# TIA_For_Photodiode.net
KiCad netlist of a schematic drawn in Altium Designer
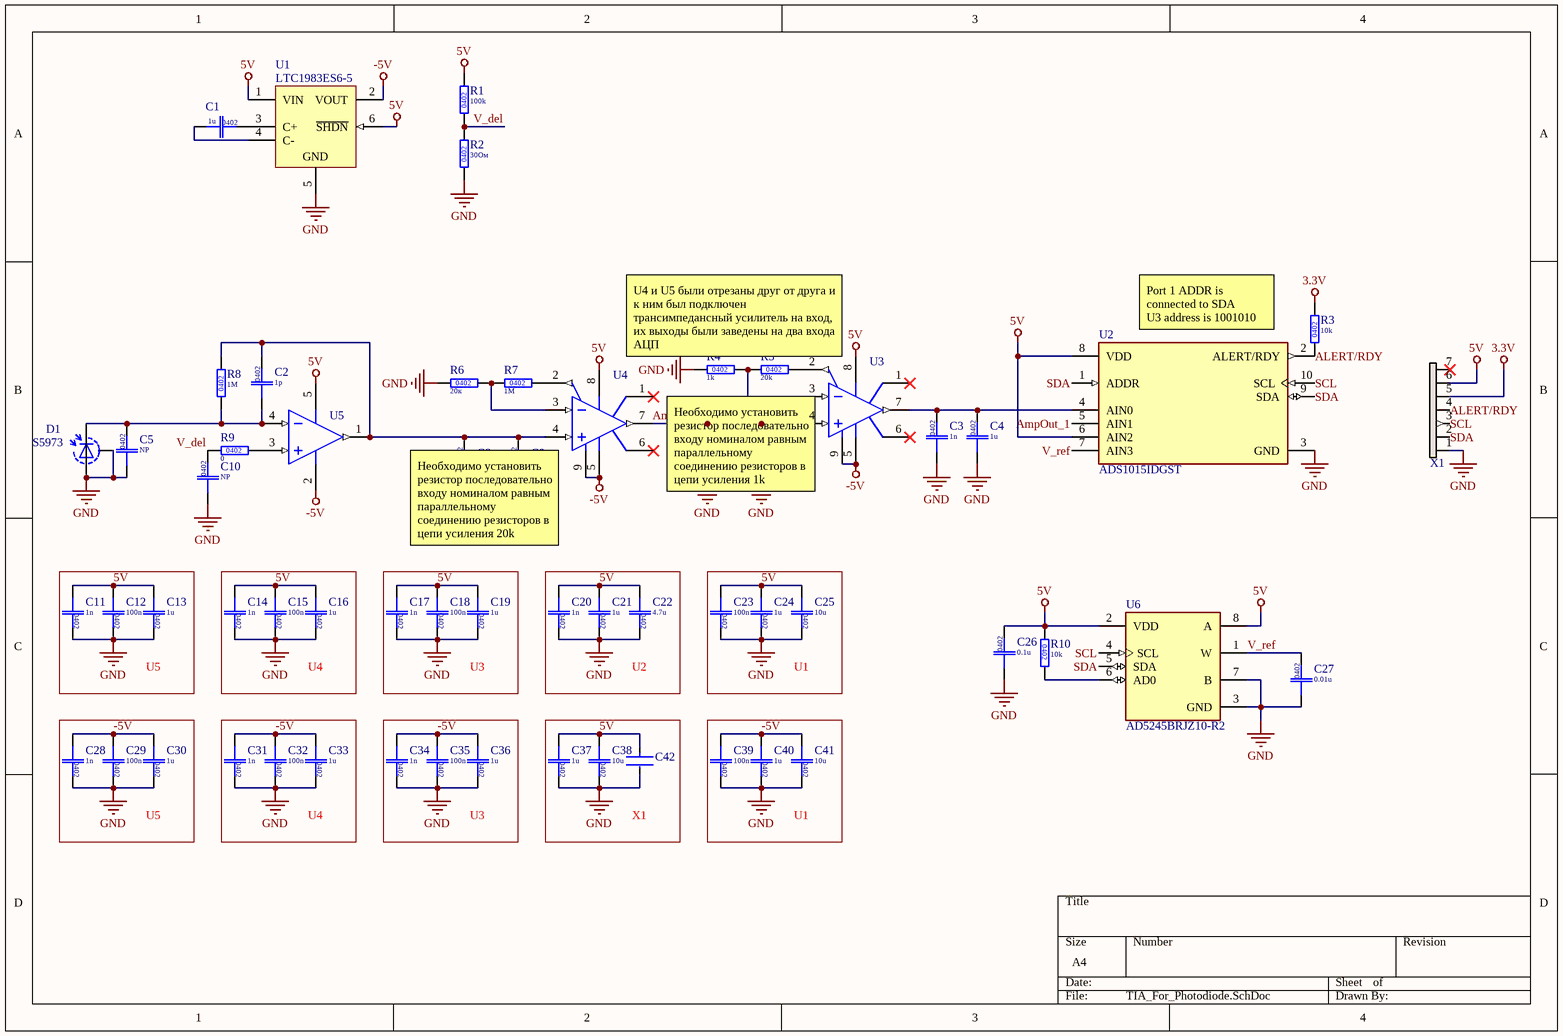
[diagram p0: TIA_For_Photodiode.SchDoc]

(export (version "E")
  (design (tool "Eeschema 10.0.6"))
  (components
    (comp (ref "C1")
      (value "1u")
      (footprint "SMD 0402")
      (fields (field (name "TOLERANCE") "10%") (field (name "VOLTAGE") "25v"))
      (libsource (lib "ComponentsDatabase") (part "Capacitor 0402"))
    )
    (comp (ref "C2")
      (value "1p")
      (footprint "SMD 0402")
      (fields (field (name "TOLERANCE") "20%") (field (name "VOLTAGE") "6,3v"))
      (libsource (lib "ComponentsDatabase") (part "Capacitor 0402"))
    )
    (comp (ref "C3")
      (value "1n")
      (footprint "SMD 0402")
      (fields (field (name "TOLERANCE") "20%") (field (name "VOLTAGE") "6,3v"))
      (libsource (lib "ComponentsDatabase") (part "Capacitor 0402"))
    )
    (comp (ref "C4")
      (value "1u")
      (footprint "SMD 0402")
      (fields (field (name "TOLERANCE") "20%") (field (name "VOLTAGE") "6,3v"))
      (libsource (lib "ComponentsDatabase") (part "Capacitor 0402"))
    )
    (comp (ref "C5")
      (value "NP")
      (footprint "SMD 0402")
      (fields (field (name "TOLERANCE") "20%") (field (name "VOLTAGE") "6,3v"))
      (libsource (lib "ComponentsDatabase") (part "Capacitor 0402"))
    )
    (comp (ref "C6")
      (value "1n")
      (footprint "SMD 0402")
      (fields (field (name "TOLERANCE") "20%") (field (name "VOLTAGE") "6,3v"))
      (libsource (lib "ComponentsDatabase") (part "Capacitor 0402"))
    )
    (comp (ref "C7")
      (value "1u")
      (footprint "SMD 0402")
      (fields (field (name "TOLERANCE") "20%") (field (name "VOLTAGE") "6,3v"))
      (libsource (lib "ComponentsDatabase") (part "Capacitor 0402"))
    )
    (comp (ref "C8")
      (value "1n")
      (footprint "SMD 0402")
      (fields (field (name "TOLERANCE") "20%") (field (name "VOLTAGE") "6,3v"))
      (libsource (lib "ComponentsDatabase") (part "Capacitor 0402"))
    )
    (comp (ref "C9")
      (value "1u")
      (footprint "SMD 0402")
      (fields (field (name "TOLERANCE") "20%") (field (name "VOLTAGE") "6,3v"))
      (libsource (lib "ComponentsDatabase") (part "Capacitor 0402"))
    )
    (comp (ref "C10")
      (value "NP")
      (footprint "SMD 0402")
      (fields (field (name "TOLERANCE") "20%") (field (name "VOLTAGE") "6,3v"))
      (libsource (lib "ComponentsDatabase") (part "Capacitor 0402"))
    )
    (comp (ref "C11")
      (value "1n")
      (footprint "SMD 0402")
      (fields (field (name "TOLERANCE") "20%") (field (name "VOLTAGE") "6,3v"))
      (libsource (lib "ComponentsDatabase") (part "Capacitor 0402"))
    )
    (comp (ref "C12")
      (value "100n")
      (footprint "SMD 0402")
      (fields (field (name "TOLERANCE") "20%") (field (name "VOLTAGE") "6,3v"))
      (libsource (lib "ComponentsDatabase") (part "Capacitor 0402"))
    )
    (comp (ref "C13")
      (value "1u")
      (footprint "SMD 0402")
      (fields (field (name "TOLERANCE") "20%") (field (name "VOLTAGE") "6,3v"))
      (libsource (lib "ComponentsDatabase") (part "Capacitor 0402"))
    )
    (comp (ref "C14")
      (value "1n")
      (footprint "SMD 0402")
      (fields (field (name "TOLERANCE") "20%") (field (name "VOLTAGE") "6,3v"))
      (libsource (lib "ComponentsDatabase") (part "Capacitor 0402"))
    )
    (comp (ref "C15")
      (value "100n")
      (footprint "SMD 0402")
      (fields (field (name "TOLERANCE") "20%") (field (name "VOLTAGE") "6,3v"))
      (libsource (lib "ComponentsDatabase") (part "Capacitor 0402"))
    )
    (comp (ref "C16")
      (value "1u")
      (footprint "SMD 0402")
      (fields (field (name "TOLERANCE") "20%") (field (name "VOLTAGE") "6,3v"))
      (libsource (lib "ComponentsDatabase") (part "Capacitor 0402"))
    )
    (comp (ref "C17")
      (value "1n")
      (footprint "SMD 0402")
      (fields (field (name "TOLERANCE") "20%") (field (name "VOLTAGE") "6,3v"))
      (libsource (lib "ComponentsDatabase") (part "Capacitor 0402"))
    )
    (comp (ref "C18")
      (value "100n")
      (footprint "SMD 0402")
      (fields (field (name "TOLERANCE") "20%") (field (name "VOLTAGE") "6,3v"))
      (libsource (lib "ComponentsDatabase") (part "Capacitor 0402"))
    )
    (comp (ref "C19")
      (value "1u")
      (footprint "SMD 0402")
      (fields (field (name "TOLERANCE") "20%") (field (name "VOLTAGE") "6,3v"))
      (libsource (lib "ComponentsDatabase") (part "Capacitor 0402"))
    )
    (comp (ref "C20")
      (value "1n")
      (footprint "SMD 0402")
      (fields (field (name "TOLERANCE") "20%") (field (name "VOLTAGE") "6,3v"))
      (libsource (lib "ComponentsDatabase") (part "Capacitor 0402"))
    )
    (comp (ref "C21")
      (value "1u")
      (footprint "SMD 0402")
      (fields (field (name "TOLERANCE") "20%") (field (name "VOLTAGE") "6,3v"))
      (libsource (lib "ComponentsDatabase") (part "Capacitor 0402"))
    )
    (comp (ref "C22")
      (value "4.7u")
      (footprint "SMD 0402")
      (fields (field (name "TOLERANCE") "20%") (field (name "VOLTAGE") "6,3v"))
      (libsource (lib "ComponentsDatabase") (part "Capacitor 0402"))
    )
    (comp (ref "C23")
      (value "100n")
      (footprint "SMD 0402")
      (fields (field (name "TOLERANCE") "20%") (field (name "VOLTAGE") "6,3v"))
      (libsource (lib "ComponentsDatabase") (part "Capacitor 0402"))
    )
    (comp (ref "C24")
      (value "1u")
      (footprint "SMD 0402")
      (fields (field (name "TOLERANCE") "20%") (field (name "VOLTAGE") "6,3v"))
      (libsource (lib "ComponentsDatabase") (part "Capacitor 0402"))
    )
    (comp (ref "C25")
      (value "10u")
      (footprint "SMD 0402")
      (fields (field (name "TOLERANCE") "20%") (field (name "VOLTAGE") "6,3v"))
      (libsource (lib "ComponentsDatabase") (part "Capacitor 0402"))
    )
    (comp (ref "C26")
      (value "0.1u")
      (footprint "SMD 0402")
      (fields (field (name "TOLERANCE") "20%") (field (name "VOLTAGE") "6,3v"))
      (libsource (lib "ComponentsDatabase") (part "Capacitor 0402"))
    )
    (comp (ref "C27")
      (value "0.01u")
      (footprint "SMD 0402")
      (fields (field (name "TOLERANCE") "20%") (field (name "VOLTAGE") "6,3v"))
      (libsource (lib "ComponentsDatabase") (part "Capacitor 0402"))
    )
    (comp (ref "C28")
      (value "1n")
      (footprint "SMD 0402")
      (fields (field (name "TOLERANCE") "20%") (field (name "VOLTAGE") "6,3v"))
      (libsource (lib "ComponentsDatabase") (part "Capacitor 0402"))
    )
    (comp (ref "C29")
      (value "100n")
      (footprint "SMD 0402")
      (fields (field (name "TOLERANCE") "20%") (field (name "VOLTAGE") "6,3v"))
      (libsource (lib "ComponentsDatabase") (part "Capacitor 0402"))
    )
    (comp (ref "C30")
      (value "1u")
      (footprint "SMD 0402")
      (fields (field (name "TOLERANCE") "20%") (field (name "VOLTAGE") "6,3v"))
      (libsource (lib "ComponentsDatabase") (part "Capacitor 0402"))
    )
    (comp (ref "C31")
      (value "1n")
      (footprint "SMD 0402")
      (fields (field (name "TOLERANCE") "20%") (field (name "VOLTAGE") "6,3v"))
      (libsource (lib "ComponentsDatabase") (part "Capacitor 0402"))
    )
    (comp (ref "C32")
      (value "100n")
      (footprint "SMD 0402")
      (fields (field (name "TOLERANCE") "20%") (field (name "VOLTAGE") "6,3v"))
      (libsource (lib "ComponentsDatabase") (part "Capacitor 0402"))
    )
    (comp (ref "C33")
      (value "1u")
      (footprint "SMD 0402")
      (fields (field (name "TOLERANCE") "20%") (field (name "VOLTAGE") "6,3v"))
      (libsource (lib "ComponentsDatabase") (part "Capacitor 0402"))
    )
    (comp (ref "C34")
      (value "1n")
      (footprint "SMD 0402")
      (fields (field (name "TOLERANCE") "20%") (field (name "VOLTAGE") "6,3v"))
      (libsource (lib "ComponentsDatabase") (part "Capacitor 0402"))
    )
    (comp (ref "C35")
      (value "100n")
      (footprint "SMD 0402")
      (fields (field (name "TOLERANCE") "20%") (field (name "VOLTAGE") "6,3v"))
      (libsource (lib "ComponentsDatabase") (part "Capacitor 0402"))
    )
    (comp (ref "C36")
      (value "1u")
      (footprint "SMD 0402")
      (fields (field (name "TOLERANCE") "20%") (field (name "VOLTAGE") "6,3v"))
      (libsource (lib "ComponentsDatabase") (part "Capacitor 0402"))
    )
    (comp (ref "C37")
      (value "1u")
      (footprint "SMD 0402")
      (fields (field (name "TOLERANCE") "20%") (field (name "VOLTAGE") "6,3v"))
      (libsource (lib "ComponentsDatabase") (part "Capacitor 0402"))
    )
    (comp (ref "C38")
      (value "10u")
      (footprint "SMD 0402")
      (fields (field (name "TOLERANCE") "20%") (field (name "VOLTAGE") "6,3v"))
      (libsource (lib "ComponentsDatabase") (part "Capacitor 0402"))
    )
    (comp (ref "C39")
      (value "100n")
      (footprint "SMD 0402")
      (fields (field (name "TOLERANCE") "20%") (field (name "VOLTAGE") "6,3v"))
      (libsource (lib "ComponentsDatabase") (part "Capacitor 0402"))
    )
    (comp (ref "C40")
      (value "1u")
      (footprint "SMD 0402")
      (fields (field (name "TOLERANCE") "20%") (field (name "VOLTAGE") "6,3v"))
      (libsource (lib "ComponentsDatabase") (part "Capacitor 0402"))
    )
    (comp (ref "C41")
      (value "10u")
      (footprint "SMD 0402")
      (fields (field (name "TOLERANCE") "20%") (field (name "VOLTAGE") "6,3v"))
      (libsource (lib "ComponentsDatabase") (part "Capacitor 0402"))
    )
    (comp (ref "C42")
      (value "GRM32ER60J107ME20L")
      (footprint "FP-GRM32-0_3-MFG")
      (description "CAP CER 100UF 6.3V X5R 1210")
      (fields
        (field (name "OCTOPART") "https://octopart.com/grm32er60j107me20l-murata-197007")
        (field (name "3DS PART NUMBER") "220-00002")
      )
      (libsource (lib "Altium Content Vault") (part "11868f565c42a9108669ba33697ecf6"))
    )
    (comp (ref "D1")
      (value "S5973")
      (footprint "TO-18")
      (description "Hamamatsu, S5973 IR + Visible Light Si PIN Photodiode, Through Hole TO-18")
      (libsource (lib "ShematicLIB") (part "S5973"))
    )
    (comp (ref "R1")
      (value "100k")
      (footprint "SMD 0402")
      (fields (field (name "TOLERANCE") "1%"))
      (libsource (lib "ComponentsDatabase") (part "Resistor 0402"))
    )
    (comp (ref "R2")
      (value "30Ом")
      (footprint "SMD 0402")
      (fields (field (name "TOLERANCE") "1%"))
      (libsource (lib "ComponentsDatabase") (part "Resistor 0402"))
    )
    (comp (ref "R3")
      (value "10k")
      (footprint "SMD 0402")
      (fields (field (name "TOLERANCE") "1%"))
      (libsource (lib "ComponentsDatabase") (part "Resistor 0402"))
    )
    (comp (ref "R4")
      (value "1k")
      (footprint "SMD 0402")
      (fields (field (name "TOLERANCE") "1%"))
      (libsource (lib "ComponentsDatabase") (part "Resistor 0402"))
    )
    (comp (ref "R5")
      (value "20k")
      (footprint "SMD 0402")
      (fields (field (name "TOLERANCE") "1%"))
      (libsource (lib "ComponentsDatabase") (part "Resistor 0402"))
    )
    (comp (ref "R6")
      (value "20к")
      (footprint "SMD 0402")
      (fields (field (name "TOLERANCE") "1%"))
      (libsource (lib "ComponentsDatabase") (part "Resistor 0402"))
    )
    (comp (ref "R7")
      (value "1М")
      (footprint "SMD 0402")
      (fields (field (name "TOLERANCE") "1%"))
      (libsource (lib "ComponentsDatabase") (part "Resistor 0402"))
    )
    (comp (ref "R8")
      (value "1М")
      (footprint "SMD 0402")
      (fields (field (name "TOLERANCE") "1%"))
      (libsource (lib "ComponentsDatabase") (part "Resistor 0402"))
    )
    (comp (ref "R9")
      (value "0")
      (footprint "SMD 0402")
      (fields (field (name "TOLERANCE") "1%"))
      (libsource (lib "ComponentsDatabase") (part "Resistor 0402"))
    )
    (comp (ref "R10")
      (value "10k")
      (footprint "SMD 0402")
      (fields (field (name "TOLERANCE") "1%"))
      (libsource (lib "ComponentsDatabase") (part "Resistor 0402"))
    )
    (comp (ref "U1")
      (value "LTC1983ES6-5")
      (footprint "LT-S6-6-TSOT-23_M")
      (fields (field (name "MANUFACTURER") "Linear Technology"))
      (libsource (lib "Altium Content Vault") (part "LT-LTC1983-S6-6"))
    )
    (comp (ref "U2")
      (value "ADS1015IDGST")
      (footprint "FP-DGS0010A-MFG")
      (description "IC ADC 12BIT SIGMA-DELTA 10VSSOP")
      (libsource (lib "Altium Content Vault") (part "0fb225032f4bd54fd540a872e776a50"))
    )
    (comp (ref "U3")
      (value "AD8045ACPZ-REEL7")
      (footprint "ADI-CP-8-2_N")
      (fields (field (name "GENERIC PART NUMBER") "AD8045") (field (name "MANUFACTURER") "Analog Devices"))
      (libsource (lib "Altium Content Vault") (part "ADI-AD8045-CP-8-2"))
    )
    (comp (ref "U4")
      (value "AD8045ACPZ-REEL7")
      (footprint "ADI-CP-8-2_N")
      (fields (field (name "GENERIC PART NUMBER") "AD8045") (field (name "MANUFACTURER") "Analog Devices"))
      (libsource (lib "Altium Content Vault") (part "ADI-AD8045-CP-8-2"))
    )
    (comp (ref "U5")
      (value "AD8065ARTZ-REEL7")
      (footprint "ADI-RJ-5_L")
      (fields (field (name "GENERIC PART NUMBER") "AD8065") (field (name "MANUFACTURER") "Analog Devices"))
      (libsource (lib "Altium Content Vault") (part "ADI-AD80XX-5"))
    )
    (comp (ref "U6")
      (value "AD5245BRJZ10-R2")
      (footprint "FP-RJ-8-IPC_C")
      (description "IC DGT POT 10KOHM 256TAP SOT23-8")
      (fields (field (name "TOLERANCE") "30%") (field (name "MANUFACTURER") "Analog Devices"))
      (libsource (lib "Altium Content Vault") (part "8d408c839f24318d0976f3536df8182"))
    )
    (comp (ref "X1")
      (value "PicoBlade 7 pins")
      (footprint "PicoBlade 7 pins")
      (libsource (lib "ShematicLIB") (part "PicoBlade 7 pins"))
    )
  )
  (nets
    (net (code "1") (name "-5V") (class "Default")
      (node (ref "C28") (pin "1") (pinfunction "1_1") (pintype "passive"))
      (node (ref "C29") (pin "1") (pinfunction "1_1") (pintype "passive"))
      (node (ref "C30") (pin "1") (pinfunction "1_1") (pintype "passive"))
      (node (ref "C31") (pin "1") (pinfunction "1_1") (pintype "passive"))
      (node (ref "C32") (pin "1") (pinfunction "1_1") (pintype "passive"))
      (node (ref "C33") (pin "1") (pinfunction "1_1") (pintype "passive"))
      (node (ref "C34") (pin "1") (pinfunction "1_1") (pintype "passive"))
      (node (ref "C35") (pin "1") (pinfunction "1_1") (pintype "passive"))
      (node (ref "C36") (pin "1") (pinfunction "1_1") (pintype "passive"))
      (node (ref "C39") (pin "1") (pinfunction "1_1") (pintype "passive"))
      (node (ref "C40") (pin "1") (pinfunction "1_1") (pintype "passive"))
      (node (ref "C41") (pin "1") (pinfunction "1_1") (pintype "passive"))
      (node (ref "U1") (pin "2") (pinfunction "VOUT_2") (pintype "power_in"))
      (node (ref "U3") (pin "5") (pinfunction "-VS_5") (pintype "power_in"))
      (node (ref "U3") (pin "9") (pinfunction "EP_9") (pintype "power_in"))
      (node (ref "U4") (pin "5") (pinfunction "-VS_5") (pintype "power_in"))
      (node (ref "U4") (pin "9") (pinfunction "EP_9") (pintype "power_in"))
      (node (ref "U5") (pin "2") (pinfunction "-VS_2") (pintype "power_in"))
    )
    (net (code "2") (name "/ALERT{slash}RDY") (class "Default")
      (node (ref "R3") (pin "1") (pinfunction "1_1") (pintype "passive"))
      (node (ref "U2") (pin "2") (pinfunction "ALERT/RDY_2") (pintype "output"))
      (node (ref "X1") (pin "4") (pinfunction "4_4") (pintype "passive"))
    )
    (net (code "3") (name "/AmpOut_1") (class "Default")
      (node (ref "C6") (pin "2") (pinfunction "2_2") (pintype "passive"))
      (node (ref "C7") (pin "2") (pinfunction "2_2") (pintype "passive"))
      (node (ref "U2") (pin "5") (pinfunction "AIN1_5") (pintype "passive"))
      (node (ref "U3") (pin "4") (pinfunction "+IN_4") (pintype "input"))
      (node (ref "U4") (pin "7") (pinfunction "OUT_7") (pintype "output"))
    )
    (net (code "4") (name "/SCL") (class "Default")
      (node (ref "U2") (pin "10") (pinfunction "SCL_10") (pintype "input"))
      (node (ref "U6") (pin "4") (pinfunction "SCL_4") (pintype "input"))
      (node (ref "X1") (pin "3") (pinfunction "3_3") (pintype "output"))
    )
    (net (code "5") (name "/SDA") (class "Default")
      (node (ref "U2") (pin "1") (pinfunction "ADDR_1") (pintype "input"))
      (node (ref "U2") (pin "9") (pinfunction "SDA_9") (pintype "bidirectional"))
      (node (ref "U6") (pin "5") (pinfunction "SDA_5") (pintype "bidirectional"))
      (node (ref "X1") (pin "2") (pinfunction "2_2") (pintype "passive"))
    )
    (net (code "6") (name "/V_del") (class "Default")
      (node (ref "C10") (pin "2") (pinfunction "2_2") (pintype "passive"))
      (node (ref "R1") (pin "1") (pinfunction "1_1") (pintype "passive"))
      (node (ref "R2") (pin "2") (pinfunction "2_2") (pintype "passive"))
      (node (ref "R9") (pin "1") (pinfunction "1_1") (pintype "passive"))
    )
    (net (code "7") (name "/V_ref") (class "Default")
      (node (ref "C27") (pin "2") (pinfunction "2_2") (pintype "passive"))
      (node (ref "U2") (pin "7") (pinfunction "AIN3_7") (pintype "passive"))
      (node (ref "U6") (pin "1") (pinfunction "W_1") (pintype "passive"))
    )
    (net (code "8") (name "3.3V") (class "Default")
      (node (ref "R3") (pin "2") (pinfunction "2_2") (pintype "passive"))
      (node (ref "X1") (pin "5") (pinfunction "5_5") (pintype "passive"))
    )
    (net (code "9") (name "5V") (class "Default")
      (node (ref "C11") (pin "1") (pinfunction "1_1") (pintype "passive"))
      (node (ref "C12") (pin "1") (pinfunction "1_1") (pintype "passive"))
      (node (ref "C13") (pin "1") (pinfunction "1_1") (pintype "passive"))
      (node (ref "C14") (pin "1") (pinfunction "1_1") (pintype "passive"))
      (node (ref "C15") (pin "1") (pinfunction "1_1") (pintype "passive"))
      (node (ref "C16") (pin "1") (pinfunction "1_1") (pintype "passive"))
      (node (ref "C17") (pin "1") (pinfunction "1_1") (pintype "passive"))
      (node (ref "C18") (pin "1") (pinfunction "1_1") (pintype "passive"))
      (node (ref "C19") (pin "1") (pinfunction "1_1") (pintype "passive"))
      (node (ref "C20") (pin "1") (pinfunction "1_1") (pintype "passive"))
      (node (ref "C21") (pin "1") (pinfunction "1_1") (pintype "passive"))
      (node (ref "C22") (pin "1") (pinfunction "1_1") (pintype "passive"))
      (node (ref "C23") (pin "1") (pinfunction "1_1") (pintype "passive"))
      (node (ref "C24") (pin "1") (pinfunction "1_1") (pintype "passive"))
      (node (ref "C25") (pin "1") (pinfunction "1_1") (pintype "passive"))
      (node (ref "C26") (pin "2") (pinfunction "2_2") (pintype "passive"))
      (node (ref "C37") (pin "1") (pinfunction "1_1") (pintype "passive"))
      (node (ref "C38") (pin "1") (pinfunction "1_1") (pintype "passive"))
      (node (ref "C42") (pin "1") (pinfunction "1_1") (pintype "passive"))
      (node (ref "R1") (pin "2") (pinfunction "2_2") (pintype "passive"))
      (node (ref "R10") (pin "1") (pinfunction "1_1") (pintype "passive"))
      (node (ref "U1") (pin "1") (pinfunction "VIN_1") (pintype "power_in"))
      (node (ref "U1") (pin "6") (pinfunction "~{SHDN}_6") (pintype "input"))
      (node (ref "U2") (pin "6") (pinfunction "AIN2_6") (pintype "passive"))
      (node (ref "U2") (pin "8") (pinfunction "VDD_8") (pintype "power_in"))
      (node (ref "U3") (pin "8") (pinfunction "+VS_8") (pintype "power_in"))
      (node (ref "U4") (pin "8") (pinfunction "+VS_8") (pintype "power_in"))
      (node (ref "U5") (pin "5") (pinfunction "+VS_5") (pintype "power_in"))
      (node (ref "U6") (pin "2") (pinfunction "VDD_2") (pintype "power_in"))
      (node (ref "U6") (pin "8") (pinfunction "A_8") (pintype "passive"))
      (node (ref "X1") (pin "6") (pinfunction "6_6") (pintype "passive"))
    )
    (net (code "10") (name "GND") (class "Default")
      (node (ref "C10") (pin "1") (pinfunction "1_1") (pintype "passive"))
      (node (ref "C11") (pin "2") (pinfunction "2_2") (pintype "passive"))
      (node (ref "C12") (pin "2") (pinfunction "2_2") (pintype "passive"))
      (node (ref "C13") (pin "2") (pinfunction "2_2") (pintype "passive"))
      (node (ref "C14") (pin "2") (pinfunction "2_2") (pintype "passive"))
      (node (ref "C15") (pin "2") (pinfunction "2_2") (pintype "passive"))
      (node (ref "C16") (pin "2") (pinfunction "2_2") (pintype "passive"))
      (node (ref "C17") (pin "2") (pinfunction "2_2") (pintype "passive"))
      (node (ref "C18") (pin "2") (pinfunction "2_2") (pintype "passive"))
      (node (ref "C19") (pin "2") (pinfunction "2_2") (pintype "passive"))
      (node (ref "C20") (pin "2") (pinfunction "2_2") (pintype "passive"))
      (node (ref "C21") (pin "2") (pinfunction "2_2") (pintype "passive"))
      (node (ref "C22") (pin "2") (pinfunction "2_2") (pintype "passive"))
      (node (ref "C23") (pin "2") (pinfunction "2_2") (pintype "passive"))
      (node (ref "C24") (pin "2") (pinfunction "2_2") (pintype "passive"))
      (node (ref "C25") (pin "2") (pinfunction "2_2") (pintype "passive"))
      (node (ref "C26") (pin "1") (pinfunction "1_1") (pintype "passive"))
      (node (ref "C27") (pin "1") (pinfunction "1_1") (pintype "passive"))
      (node (ref "C28") (pin "2") (pinfunction "2_2") (pintype "passive"))
      (node (ref "C29") (pin "2") (pinfunction "2_2") (pintype "passive"))
      (node (ref "C3") (pin "1") (pinfunction "1_1") (pintype "passive"))
      (node (ref "C30") (pin "2") (pinfunction "2_2") (pintype "passive"))
      (node (ref "C31") (pin "2") (pinfunction "2_2") (pintype "passive"))
      (node (ref "C32") (pin "2") (pinfunction "2_2") (pintype "passive"))
      (node (ref "C33") (pin "2") (pinfunction "2_2") (pintype "passive"))
      (node (ref "C34") (pin "2") (pinfunction "2_2") (pintype "passive"))
      (node (ref "C35") (pin "2") (pinfunction "2_2") (pintype "passive"))
      (node (ref "C36") (pin "2") (pinfunction "2_2") (pintype "passive"))
      (node (ref "C37") (pin "2") (pinfunction "2_2") (pintype "passive"))
      (node (ref "C38") (pin "2") (pinfunction "2_2") (pintype "passive"))
      (node (ref "C39") (pin "2") (pinfunction "2_2") (pintype "passive"))
      (node (ref "C4") (pin "1") (pinfunction "1_1") (pintype "passive"))
      (node (ref "C40") (pin "2") (pinfunction "2_2") (pintype "passive"))
      (node (ref "C41") (pin "2") (pinfunction "2_2") (pintype "passive"))
      (node (ref "C42") (pin "2") (pinfunction "2_2") (pintype "passive"))
      (node (ref "C5") (pin "1") (pinfunction "1_1") (pintype "passive"))
      (node (ref "C6") (pin "1") (pinfunction "1_1") (pintype "passive"))
      (node (ref "C7") (pin "1") (pinfunction "1_1") (pintype "passive"))
      (node (ref "C8") (pin "1") (pinfunction "1_1") (pintype "passive"))
      (node (ref "C9") (pin "1") (pinfunction "1_1") (pintype "passive"))
      (node (ref "D1") (pin "2") (pinfunction "S_2") (pintype "passive"))
      (node (ref "D1") (pin "3") (pinfunction "A_3") (pintype "passive"))
      (node (ref "R2") (pin "1") (pinfunction "1_1") (pintype "passive"))
      (node (ref "R4") (pin "1") (pinfunction "1_1") (pintype "passive"))
      (node (ref "R6") (pin "1") (pinfunction "1_1") (pintype "passive"))
      (node (ref "U1") (pin "5") (pinfunction "GND_5") (pintype "power_in"))
      (node (ref "U2") (pin "3") (pinfunction "GND_3") (pintype "power_in"))
      (node (ref "U6") (pin "3") (pinfunction "GND_3") (pintype "power_in"))
      (node (ref "U6") (pin "7") (pinfunction "B_7") (pintype "passive"))
      (node (ref "X1") (pin "1") (pinfunction "1_1") (pintype "passive"))
    )
    (net (code "11") (name "Net-(D1-C)") (class "Default")
      (node (ref "C2") (pin "1") (pinfunction "1_1") (pintype "passive"))
      (node (ref "C5") (pin "2") (pinfunction "2_2") (pintype "passive"))
      (node (ref "D1") (pin "1") (pinfunction "C_1") (pintype "passive"))
      (node (ref "R8") (pin "1") (pinfunction "1_1") (pintype "passive"))
      (node (ref "U5") (pin "4") (pinfunction "-IN_4") (pintype "input"))
    )
    (net (code "12") (name "Net-(U1-C+)") (class "Default")
      (node (ref "C1") (pin "2") (pinfunction "2_2") (pintype "passive"))
      (node (ref "U1") (pin "3") (pinfunction "C+_3") (pintype "passive"))
    )
    (net (code "13") (name "Net-(U1-C-)") (class "Default")
      (node (ref "C1") (pin "1") (pinfunction "1_1") (pintype "passive"))
      (node (ref "U1") (pin "4") (pinfunction "C-_4") (pintype "passive"))
    )
    (net (code "14") (name "Net-(U2-AIN0)") (class "Default")
      (node (ref "C3") (pin "2") (pinfunction "2_2") (pintype "passive"))
      (node (ref "C4") (pin "2") (pinfunction "2_2") (pintype "passive"))
      (node (ref "U2") (pin "4") (pinfunction "AIN0_4") (pintype "passive"))
      (node (ref "U3") (pin "7") (pinfunction "OUT_7") (pintype "output"))
    )
    (net (code "15") (name "Net-(U3--IN)") (class "Default")
      (node (ref "R4") (pin "2") (pinfunction "2_2") (pintype "passive"))
      (node (ref "R5") (pin "1") (pinfunction "1_1") (pintype "passive"))
      (node (ref "U3") (pin "3") (pinfunction "-IN_3") (pintype "input"))
    )
    (net (code "16") (name "Net-(U3-FEEDBACK)") (class "Default")
      (node (ref "R5") (pin "2") (pinfunction "2_2") (pintype "passive"))
      (node (ref "U3") (pin "2") (pinfunction "FEEDBACK_2") (pintype "output"))
    )
    (net (code "17") (name "Net-(U4-+IN)") (class "Default")
      (node (ref "C2") (pin "2") (pinfunction "2_2") (pintype "passive"))
      (node (ref "C8") (pin "2") (pinfunction "2_2") (pintype "passive"))
      (node (ref "C9") (pin "2") (pinfunction "2_2") (pintype "passive"))
      (node (ref "R8") (pin "2") (pinfunction "2_2") (pintype "passive"))
      (node (ref "U4") (pin "4") (pinfunction "+IN_4") (pintype "input"))
      (node (ref "U5") (pin "1") (pinfunction "VOUT_1") (pintype "output"))
    )
    (net (code "18") (name "Net-(U4--IN)") (class "Default")
      (node (ref "R6") (pin "2") (pinfunction "2_2") (pintype "passive"))
      (node (ref "R7") (pin "1") (pinfunction "1_1") (pintype "passive"))
      (node (ref "U4") (pin "3") (pinfunction "-IN_3") (pintype "input"))
    )
    (net (code "19") (name "Net-(U4-FEEDBACK)") (class "Default")
      (node (ref "R7") (pin "2") (pinfunction "2_2") (pintype "passive"))
      (node (ref "U4") (pin "2") (pinfunction "FEEDBACK_2") (pintype "output"))
    )
    (net (code "20") (name "Net-(U5-+IN)") (class "Default")
      (node (ref "R9") (pin "2") (pinfunction "2_2") (pintype "passive"))
      (node (ref "U5") (pin "3") (pinfunction "+IN_3") (pintype "input"))
    )
    (net (code "21") (name "Net-(U6-AD0)") (class "Default")
      (node (ref "R10") (pin "2") (pinfunction "2_2") (pintype "passive"))
      (node (ref "U6") (pin "6") (pinfunction "AD0_6") (pintype "bidirectional"))
    )
    (net (code "22") (name "unconnected-(U3-NC-Pad1)") (class "Default")
      (node (ref "U3") (pin "1") (pinfunction "NC_1") (pintype "passive+no_connect"))
    )
    (net (code "23") (name "unconnected-(U3-NC-Pad6)") (class "Default")
      (node (ref "U3") (pin "6") (pinfunction "NC_6") (pintype "passive+no_connect"))
    )
    (net (code "24") (name "unconnected-(U4-NC-Pad1)") (class "Default")
      (node (ref "U4") (pin "1") (pinfunction "NC_1") (pintype "passive+no_connect"))
    )
    (net (code "25") (name "unconnected-(U4-NC-Pad6)") (class "Default")
      (node (ref "U4") (pin "6") (pinfunction "NC_6") (pintype "passive+no_connect"))
    )
    (net (code "26") (name "unconnected-(X1-Pad7)") (class "Default")
      (node (ref "X1") (pin "7") (pinfunction "7_7") (pintype "passive+no_connect"))
    )
  )
)
